# V2.net
KiCad netlist of a schematic drawn in EAGLE
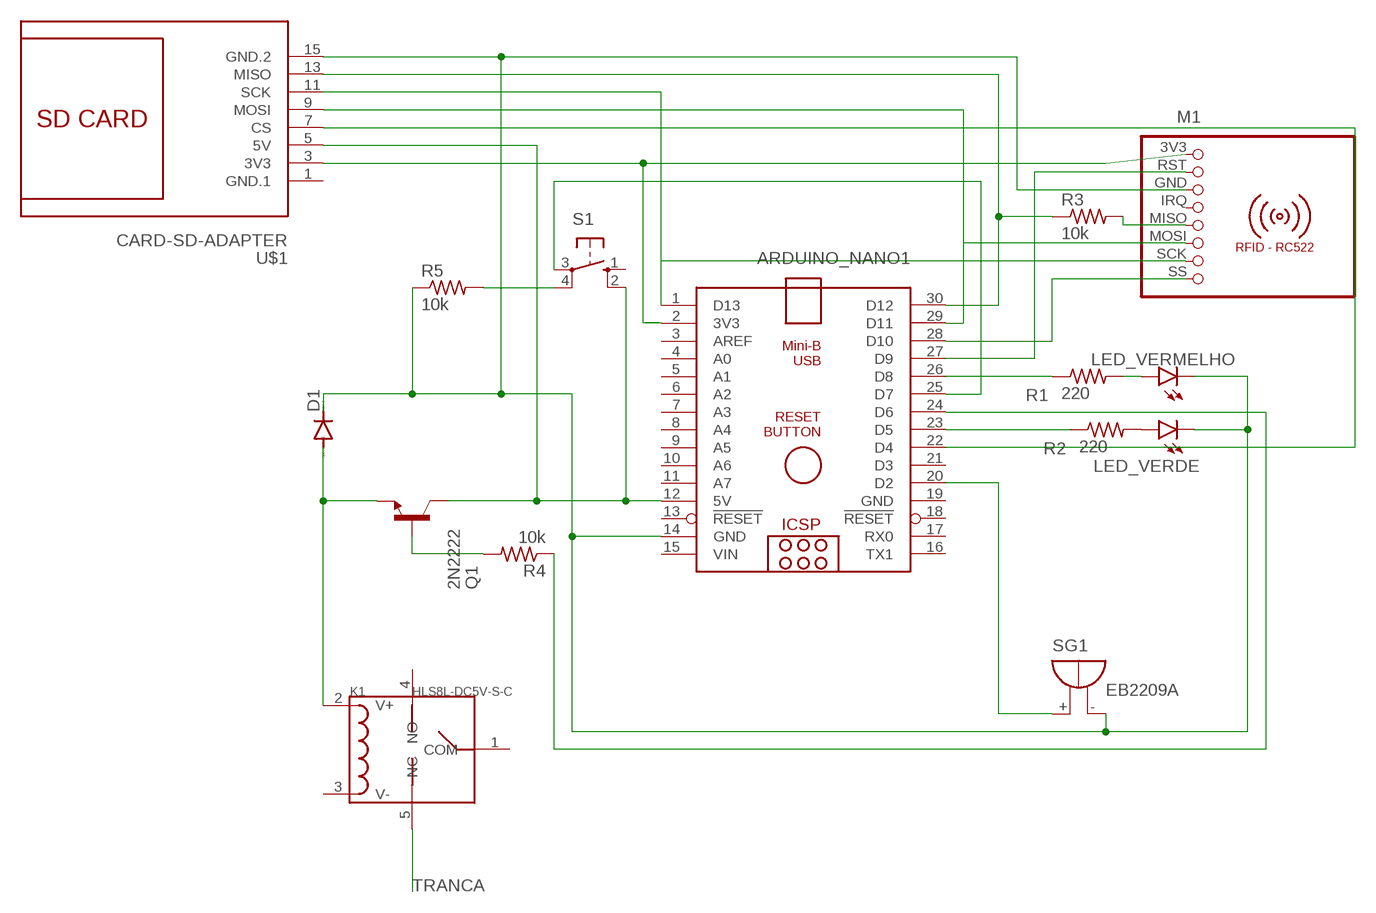
[diagram p0: schematic, sheet 1]

(export (version "E")
  (design (tool "Eeschema 10.0.6"))
  (components
    (comp (ref "ARDUINO_NANO1")
      (value "ARDUINO_NANO")
      (footprint "eagle-import:ARDUINO_NANO")
      (libsource (lib "eagle-import") (part "ARDUINO_NANO"))
    )
    (comp (ref "D1")
      (value "1N4148DO35-10")
      (footprint "eagle-import:DO35-10")
      (libsource (lib "eagle-import") (part "1N4148DO35-10"))
    )
    (comp (ref "K1")
      (value "HLS8L-DC5V-S-C")
      (footprint "eagle-import:REY5-19.0X15.0X15.0MM")
      (libsource (lib "eagle-import") (part "RELAY-HLS8L-DC5V-S-C(5P-19X15MM)"))
    )
    (comp (ref "LED_VERDE")
      (value "-LED")
      (footprint "eagle-import:LED5")
      (libsource (lib "eagle-import") (part "-LED"))
    )
    (comp (ref "LED_VERMELHO")
      (value "-LED")
      (footprint "eagle-import:LED5")
      (libsource (lib "eagle-import") (part "-LED"))
    )
    (comp (ref "M1")
      (value "RFID-RC522")
      (footprint "eagle-import:RFID-RC522")
      (libsource (lib "eagle-import") (part "RFID-RC522"))
    )
    (comp (ref "Q1")
      (value "2N2222")
      (footprint "eagle-import:TO92-CBE")
      (libsource (lib "eagle-import") (part "2N2222"))
    )
    (comp (ref "R1")
      (value "220")
      (footprint "eagle-import:0204_5")
      (libsource (lib "eagle-import") (part "R-US_0204/5"))
    )
    (comp (ref "R2")
      (value "220")
      (footprint "eagle-import:0204_5")
      (libsource (lib "eagle-import") (part "R-US_0204/5"))
    )
    (comp (ref "R3")
      (value "10k")
      (footprint "eagle-import:0204_5")
      (libsource (lib "eagle-import") (part "R-US_0204/5"))
    )
    (comp (ref "R4")
      (value "10k")
      (footprint "eagle-import:0204_5")
      (libsource (lib "eagle-import") (part "R-US_0204/5"))
    )
    (comp (ref "R5")
      (value "10k")
      (footprint "eagle-import:0204_5")
      (libsource (lib "eagle-import") (part "R-US_0204/5"))
    )
    (comp (ref "S1")
      (value "10-XX")
      (footprint "eagle-import:B3F-10XX")
      (fields (field (name "MPN") "B3F-1000"))
      (libsource (lib "eagle-import") (part "10-XX"))
    )
    (comp (ref "SG1")
      (value "EB2209A")
      (footprint "eagle-import:EB2209A")
      (libsource (lib "eagle-import") (part "EB2209A"))
    )
    (comp (ref "U$1")
      (value "CARD-SD-ADAPTER")
      (footprint "eagle-import:CARD-SD-ADAPTER")
      (libsource (lib "eagle-import") (part "CARD-SD-ADAPTER"))
    )
  )
  (nets
    (net (code "1") (name "/GND") (class "Default")
      (node (ref "ARDUINO_NANO1") (pin "19") (pinfunction "GND_19") (pintype "power_in"))
    )
    (net (code "2") (name "/GND.1") (class "Default")
      (node (ref "U$1") (pin "1") (pinfunction "GND.1_1") (pintype "power_in"))
    )
    (net (code "3") (name "/TRANCA") (class "Default")
      (node (ref "K1") (pin "5") (pinfunction "NC_5") (pintype "bidirectional"))
    )
    (net (code "4") (name "/VIN") (class "Default")
      (node (ref "ARDUINO_NANO1") (pin "15") (pinfunction "VIN_15") (pintype "power_in"))
    )
    (net (code "5") (name "Net-(ARDUINO_NANO1-3V3)") (class "Default")
      (node (ref "ARDUINO_NANO1") (pin "2") (pinfunction "3V3_2") (pintype "output"))
      (node (ref "M1") (pin "3V3") (pinfunction "1_3V3") (pintype "passive"))
      (node (ref "U$1") (pin "3") (pinfunction "3V3_3") (pintype "power_in"))
    )
    (net (code "6") (name "Net-(ARDUINO_NANO1-5V)") (class "Default")
      (node (ref "ARDUINO_NANO1") (pin "12") (pinfunction "5V_12") (pintype "power_in"))
      (node (ref "Q1") (pin "C") (pinfunction "C_C") (pintype "passive"))
      (node (ref "S1") (pin "2") (pinfunction "S1_2") (pintype "passive"))
      (node (ref "U$1") (pin "5") (pinfunction "5V_5") (pintype "power_in"))
    )
    (net (code "7") (name "Net-(ARDUINO_NANO1-D2)") (class "Default")
      (node (ref "ARDUINO_NANO1") (pin "20") (pinfunction "D2_20") (pintype "bidirectional"))
      (node (ref "SG1") (pin "+") (pinfunction "+_+") (pintype "passive"))
    )
    (net (code "8") (name "Net-(ARDUINO_NANO1-D4)") (class "Default")
      (node (ref "ARDUINO_NANO1") (pin "22") (pinfunction "D4_22") (pintype "bidirectional"))
      (node (ref "U$1") (pin "7") (pinfunction "CS_7") (pintype "bidirectional"))
    )
    (net (code "9") (name "Net-(ARDUINO_NANO1-D5)") (class "Default")
      (node (ref "ARDUINO_NANO1") (pin "23") (pinfunction "D5_23") (pintype "bidirectional"))
      (node (ref "R2") (pin "1") (pinfunction "1_1") (pintype "passive"))
    )
    (net (code "10") (name "Net-(ARDUINO_NANO1-D6)") (class "Default")
      (node (ref "ARDUINO_NANO1") (pin "24") (pinfunction "D6_24") (pintype "bidirectional"))
      (node (ref "R4") (pin "1") (pinfunction "1_1") (pintype "passive"))
    )
    (net (code "11") (name "Net-(ARDUINO_NANO1-D7)") (class "Default")
      (node (ref "ARDUINO_NANO1") (pin "25") (pinfunction "D7_25") (pintype "bidirectional"))
      (node (ref "S1") (pin "3") (pinfunction "P_3") (pintype "passive"))
    )
    (net (code "12") (name "Net-(ARDUINO_NANO1-D8)") (class "Default")
      (node (ref "ARDUINO_NANO1") (pin "26") (pinfunction "D8_26") (pintype "bidirectional"))
      (node (ref "R1") (pin "1") (pinfunction "1_1") (pintype "passive"))
    )
    (net (code "13") (name "Net-(ARDUINO_NANO1-D9)") (class "Default")
      (node (ref "ARDUINO_NANO1") (pin "27") (pinfunction "D9_27") (pintype "bidirectional"))
      (node (ref "M1") (pin "RST") (pinfunction "2_RST") (pintype "passive"))
    )
    (net (code "14") (name "Net-(ARDUINO_NANO1-D10)") (class "Default")
      (node (ref "ARDUINO_NANO1") (pin "28") (pinfunction "D10_28") (pintype "bidirectional"))
      (node (ref "M1") (pin "SS") (pinfunction "8_SS") (pintype "passive"))
    )
    (net (code "15") (name "Net-(ARDUINO_NANO1-D11)") (class "Default")
      (node (ref "ARDUINO_NANO1") (pin "29") (pinfunction "D11_29") (pintype "bidirectional"))
      (node (ref "M1") (pin "MOSI") (pinfunction "6_MOSI") (pintype "passive"))
      (node (ref "U$1") (pin "9") (pinfunction "MOSI_9") (pintype "bidirectional"))
    )
    (net (code "16") (name "Net-(ARDUINO_NANO1-D12)") (class "Default")
      (node (ref "ARDUINO_NANO1") (pin "30") (pinfunction "D12_30") (pintype "bidirectional"))
      (node (ref "R3") (pin "1") (pinfunction "1_1") (pintype "passive"))
      (node (ref "U$1") (pin "13") (pinfunction "MISO_13") (pintype "bidirectional"))
    )
    (net (code "17") (name "Net-(ARDUINO_NANO1-D13)") (class "Default")
      (node (ref "ARDUINO_NANO1") (pin "1") (pinfunction "D13_1") (pintype "bidirectional"))
      (node (ref "M1") (pin "SCK") (pinfunction "7_SCK") (pintype "passive"))
      (node (ref "U$1") (pin "11") (pinfunction "SCK_11") (pintype "bidirectional"))
    )
    (net (code "18") (name "Net-(K1-V+)") (class "Default")
      (node (ref "D1") (pin "A") (pinfunction "A_A") (pintype "passive"))
      (node (ref "K1") (pin "2") (pinfunction "V+_2") (pintype "bidirectional"))
      (node (ref "Q1") (pin "E") (pinfunction "E_E") (pintype "passive"))
    )
    (net (code "19") (name "Net-(LED_VERDE-PadANODE)") (class "Default")
      (node (ref "LED_VERDE") (pin "ANODE") (pinfunction "ANODE_ANODE") (pintype "passive"))
      (node (ref "R2") (pin "2") (pinfunction "2_2") (pintype "passive"))
    )
    (net (code "20") (name "Net-(LED_VERMELHO-PadANODE)") (class "Default")
      (node (ref "LED_VERMELHO") (pin "ANODE") (pinfunction "ANODE_ANODE") (pintype "passive"))
      (node (ref "R1") (pin "2") (pinfunction "2_2") (pintype "passive"))
    )
    (net (code "21") (name "Net-(M1-3)") (class "Default")
      (node (ref "ARDUINO_NANO1") (pin "14") (pinfunction "GND_14") (pintype "power_in"))
      (node (ref "D1") (pin "C") (pinfunction "C_C") (pintype "passive"))
      (node (ref "LED_VERDE") (pin "CATHODE") (pinfunction "CATHODE_CATHODE") (pintype "passive"))
      (node (ref "LED_VERMELHO") (pin "CATHODE") (pinfunction "CATHODE_CATHODE") (pintype "passive"))
      (node (ref "M1") (pin "GND") (pinfunction "3_GND") (pintype "passive"))
      (node (ref "R5") (pin "1") (pinfunction "1_1") (pintype "passive"))
      (node (ref "SG1") (pin "-") (pinfunction "-_-") (pintype "passive"))
      (node (ref "U$1") (pin "15") (pinfunction "GND.2_15") (pintype "power_in"))
    )
    (net (code "22") (name "Net-(M1-5)") (class "Default")
      (node (ref "M1") (pin "MISO") (pinfunction "5_MISO") (pintype "passive"))
      (node (ref "R3") (pin "2") (pinfunction "2_2") (pintype "passive"))
    )
    (net (code "23") (name "Net-(Q1-PadB)") (class "Default")
      (node (ref "Q1") (pin "B") (pinfunction "B_B") (pintype "passive"))
      (node (ref "R4") (pin "2") (pinfunction "2_2") (pintype "passive"))
    )
    (net (code "24") (name "Net-(S1-P1)") (class "Default")
      (node (ref "R5") (pin "2") (pinfunction "2_2") (pintype "passive"))
      (node (ref "S1") (pin "4") (pinfunction "P1_4") (pintype "passive"))
    )
    (net (code "25") (name "unconnected-(ARDUINO_NANO1-A0-Pad4)") (class "Default")
      (node (ref "ARDUINO_NANO1") (pin "4") (pinfunction "A0_4") (pintype "bidirectional"))
    )
    (net (code "26") (name "unconnected-(ARDUINO_NANO1-A1-Pad5)") (class "Default")
      (node (ref "ARDUINO_NANO1") (pin "5") (pinfunction "A1_5") (pintype "bidirectional"))
    )
    (net (code "27") (name "unconnected-(ARDUINO_NANO1-A2-Pad6)") (class "Default")
      (node (ref "ARDUINO_NANO1") (pin "6") (pinfunction "A2_6") (pintype "bidirectional"))
    )
    (net (code "28") (name "unconnected-(ARDUINO_NANO1-A3-Pad7)") (class "Default")
      (node (ref "ARDUINO_NANO1") (pin "7") (pinfunction "A3_7") (pintype "bidirectional"))
    )
    (net (code "29") (name "unconnected-(ARDUINO_NANO1-A4-Pad8)") (class "Default")
      (node (ref "ARDUINO_NANO1") (pin "8") (pinfunction "A4_8") (pintype "bidirectional"))
    )
    (net (code "30") (name "unconnected-(ARDUINO_NANO1-A5-Pad9)") (class "Default")
      (node (ref "ARDUINO_NANO1") (pin "9") (pinfunction "A5_9") (pintype "bidirectional"))
    )
    (net (code "31") (name "unconnected-(ARDUINO_NANO1-A6-Pad10)") (class "Default")
      (node (ref "ARDUINO_NANO1") (pin "10") (pinfunction "A6_10") (pintype "bidirectional"))
    )
    (net (code "32") (name "unconnected-(ARDUINO_NANO1-A7-Pad11)") (class "Default")
      (node (ref "ARDUINO_NANO1") (pin "11") (pinfunction "A7_11") (pintype "bidirectional"))
    )
    (net (code "33") (name "unconnected-(ARDUINO_NANO1-AREF-Pad3)") (class "Default")
      (node (ref "ARDUINO_NANO1") (pin "3") (pinfunction "AREF_3") (pintype "input"))
    )
    (net (code "34") (name "unconnected-(ARDUINO_NANO1-D3-Pad21)") (class "Default")
      (node (ref "ARDUINO_NANO1") (pin "21") (pinfunction "D3_21") (pintype "bidirectional"))
    )
    (net (code "35") (name "unconnected-(ARDUINO_NANO1-RX0-Pad17)") (class "Default")
      (node (ref "ARDUINO_NANO1") (pin "17") (pinfunction "RX0_17") (pintype "bidirectional"))
    )
    (net (code "36") (name "unconnected-(ARDUINO_NANO1-TX1-Pad16)") (class "Default")
      (node (ref "ARDUINO_NANO1") (pin "16") (pinfunction "TX1_16") (pintype "bidirectional"))
    )
    (net (code "37") (name "unconnected-(ARDUINO_NANO1-~{RESET}-Pad13)") (class "Default")
      (node (ref "ARDUINO_NANO1") (pin "13") (pinfunction "~{RESET}_13") (pintype "input"))
    )
    (net (code "38") (name "unconnected-(ARDUINO_NANO1-~{RESET}-Pad18)") (class "Default")
      (node (ref "ARDUINO_NANO1") (pin "18") (pinfunction "~{RESET}_18") (pintype "input"))
    )
    (net (code "39") (name "unconnected-(K1-COM-Pad1)") (class "Default")
      (node (ref "K1") (pin "1") (pinfunction "COM_1") (pintype "bidirectional"))
    )
    (net (code "40") (name "unconnected-(K1-NO-Pad4)") (class "Default")
      (node (ref "K1") (pin "4") (pinfunction "NO_4") (pintype "bidirectional"))
    )
    (net (code "41") (name "unconnected-(K1-V--Pad3)") (class "Default")
      (node (ref "K1") (pin "3") (pinfunction "V-_3") (pintype "bidirectional"))
    )
    (net (code "42") (name "unconnected-(M1-4-PadIRQ)") (class "Default")
      (node (ref "M1") (pin "IRQ") (pinfunction "4_IRQ") (pintype "passive"))
    )
    (net (code "43") (name "unconnected-(S1-S-Pad1)") (class "Default")
      (node (ref "S1") (pin "1") (pinfunction "S_1") (pintype "passive"))
    )
  )
)
